# SchematicPULPiniMCU.net
KiCad netlist of a schematic drawn in Altium Designer
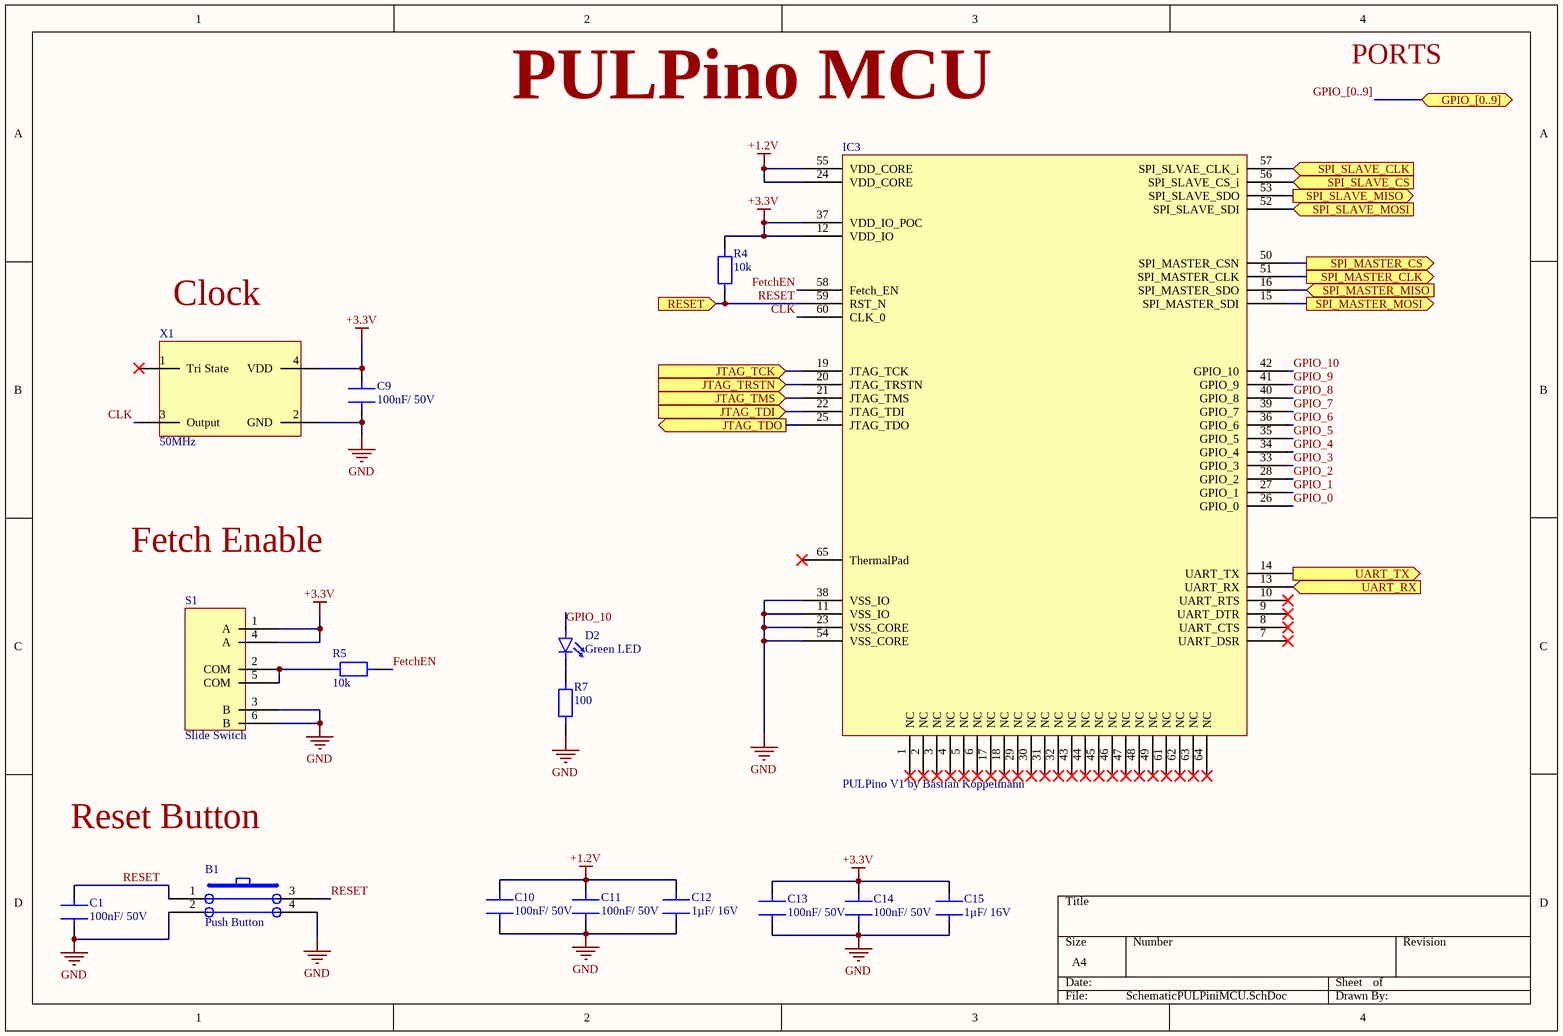
[diagram p0: SchematicPULPiniMCU.SchDoc]

(export (version "E")
  (design (tool "Eeschema 10.0.6"))
  (components
    (comp (ref "B1")
      (value "Push Button")
      (footprint "PUSH Switch")
      (description "PTS647SM50SMTR2LFS")
      (libsource (lib "upbracing_library") (part "Push Button PTS647SM50SMTR2LFS"))
    )
    (comp (ref "C1")
      (value "100nF/ 50V")
      (footprint "C0603")
      (description "C0603/C0805")
      (libsource (lib "upbracing_library") (part "C 100nF/ 50V"))
    )
    (comp (ref "C9")
      (value "100nF/ 50V")
      (footprint "C0603")
      (description "C0603/C0805")
      (libsource (lib "upbracing_library") (part "C 100nF/ 50V"))
    )
    (comp (ref "C10")
      (value "100nF/ 50V")
      (footprint "C0603")
      (description "C0603/C0805")
      (libsource (lib "upbracing_library") (part "C 100nF/ 50V"))
    )
    (comp (ref "C11")
      (value "100nF/ 50V")
      (footprint "C0603")
      (description "C0603/C0805")
      (libsource (lib "upbracing_library") (part "C 100nF/ 50V"))
    )
    (comp (ref "C12")
      (value "1µF/ 16V")
      (footprint "C0603")
      (description "C0603/C0805")
      (libsource (lib "upbracing_library") (part "C 1µF/ 16V"))
    )
    (comp (ref "C13")
      (value "100nF/ 50V")
      (footprint "C0603")
      (description "C0603/C0805")
      (libsource (lib "upbracing_library") (part "C 100nF/ 50V"))
    )
    (comp (ref "C14")
      (value "100nF/ 50V")
      (footprint "C0603")
      (description "C0603/C0805")
      (libsource (lib "upbracing_library") (part "C 100nF/ 50V"))
    )
    (comp (ref "C15")
      (value "1µF/ 16V")
      (footprint "C0603")
      (description "C0603/C0805")
      (libsource (lib "upbracing_library") (part "C 1µF/ 16V"))
    )
    (comp (ref "D2")
      (value "Green LED")
      (footprint "LED_0805")
      (description "Status LED")
      (libsource (lib "upbracing_library") (part "LED 0805"))
    )
    (comp (ref "IC3")
      (value "PULPino V1 by Bastian Koppelmann")
      (footprint "MQFN 64-Lead 9mm P=0.5mm")
      (description "Version 1 PULPino by Bastian Koppelmann")
      (libsource (lib "upbracing_library") (part "MCU PULPino V1 QFN64"))
    )
    (comp (ref "R4")
      (value "10k")
      (footprint "R0603")
      (description "0805")
      (libsource (lib "upbracing_library") (part "RES_10k"))
    )
    (comp (ref "R5")
      (value "10k")
      (footprint "R0603")
      (description "0805")
      (libsource (lib "upbracing_library") (part "RES_10k"))
    )
    (comp (ref "R7")
      (value "100")
      (footprint "R0603")
      (description "0603/0805")
      (libsource (lib "upbracing_library") (part "RES_100"))
    )
    (comp (ref "S1")
      (value "Slide Switch")
      (footprint "Slide Switch WE 452403012014")
      (description "Slide Switch, WE 452403012014")
      (libsource (lib "upbracing_library") (part "Slide Switch WE 452403012014"))
    )
    (comp (ref "X1")
      (value "50MHz")
      (footprint "QFN 2520 SiT1602 Oscillators 2.5x2.0mm")
      (description "Oscillator 50MHz. Pin 1 NC")
      (libsource (lib "upbracing_library") (part "SiT1602BC-11-33N-50.000000"))
    )
  )
  (nets
    (net (code "1") (name "+1.2V") (class "Default")
      (node (ref "C10") (pin "2") (pinfunction "2_2") (pintype "passive"))
      (node (ref "C11") (pin "2") (pinfunction "2_2") (pintype "passive"))
      (node (ref "C12") (pin "2") (pinfunction "2_2") (pintype "passive"))
      (node (ref "IC3") (pin "24") (pinfunction "VDD_CORE_24") (pintype "passive"))
      (node (ref "IC3") (pin "55") (pinfunction "VDD_CORE_55") (pintype "passive"))
    )
    (net (code "2") (name "+3.3V") (class "Default")
      (node (ref "C13") (pin "2") (pinfunction "2_2") (pintype "passive"))
      (node (ref "C14") (pin "2") (pinfunction "2_2") (pintype "passive"))
      (node (ref "C15") (pin "2") (pinfunction "2_2") (pintype "passive"))
      (node (ref "C9") (pin "1") (pinfunction "1_1") (pintype "passive"))
      (node (ref "IC3") (pin "12") (pinfunction "VDD_IO_12") (pintype "passive"))
      (node (ref "IC3") (pin "37") (pinfunction "VDD_IO_POC_37") (pintype "passive"))
      (node (ref "R4") (pin "2") (pinfunction "2_2") (pintype "passive"))
      (node (ref "S1") (pin "1") (pinfunction "A_1") (pintype "passive"))
      (node (ref "S1") (pin "4") (pinfunction "A_4") (pintype "passive"))
      (node (ref "X1") (pin "4") (pinfunction "VDD_4") (pintype "passive"))
    )
    (net (code "3") (name "/CLK") (class "Default")
      (node (ref "IC3") (pin "60") (pinfunction "CLK_0_60") (pintype "passive"))
      (node (ref "X1") (pin "3") (pinfunction "Output_3") (pintype "passive"))
    )
    (net (code "4") (name "/FetchEN") (class "Default")
      (node (ref "IC3") (pin "58") (pinfunction "Fetch_EN_58") (pintype "passive"))
      (node (ref "R5") (pin "2") (pinfunction "2_2") (pintype "passive"))
    )
    (net (code "5") (name "/GPIO_0") (class "Default")
      (node (ref "IC3") (pin "26") (pinfunction "GPIO_0_26") (pintype "passive"))
    )
    (net (code "6") (name "/GPIO_1") (class "Default")
      (node (ref "IC3") (pin "27") (pinfunction "GPIO_1_27") (pintype "passive"))
    )
    (net (code "7") (name "/GPIO_2") (class "Default")
      (node (ref "IC3") (pin "28") (pinfunction "GPIO_2_28") (pintype "passive"))
    )
    (net (code "8") (name "/GPIO_3") (class "Default")
      (node (ref "IC3") (pin "33") (pinfunction "GPIO_3_33") (pintype "passive"))
    )
    (net (code "9") (name "/GPIO_4") (class "Default")
      (node (ref "IC3") (pin "34") (pinfunction "GPIO_4_34") (pintype "passive"))
    )
    (net (code "10") (name "/GPIO_5") (class "Default")
      (node (ref "IC3") (pin "35") (pinfunction "GPIO_5_35") (pintype "passive"))
    )
    (net (code "11") (name "/GPIO_6") (class "Default")
      (node (ref "IC3") (pin "36") (pinfunction "GPIO_6_36") (pintype "passive"))
    )
    (net (code "12") (name "/GPIO_7") (class "Default")
      (node (ref "IC3") (pin "39") (pinfunction "GPIO_7_39") (pintype "passive"))
    )
    (net (code "13") (name "/GPIO_8") (class "Default")
      (node (ref "IC3") (pin "40") (pinfunction "GPIO_8_40") (pintype "passive"))
    )
    (net (code "14") (name "/GPIO_9") (class "Default")
      (node (ref "IC3") (pin "41") (pinfunction "GPIO_9_41") (pintype "passive"))
    )
    (net (code "15") (name "/GPIO_10") (class "Default")
      (node (ref "D2") (pin "1") (pinfunction "1_1") (pintype "passive"))
      (node (ref "IC3") (pin "42") (pinfunction "GPIO_10_42") (pintype "passive"))
    )
    (net (code "17") (name "/JTAG_TCK") (class "Default")
      (node (ref "IC3") (pin "19") (pinfunction "JTAG_TCK_19") (pintype "passive"))
    )
    (net (code "18") (name "/JTAG_TDI") (class "Default")
      (node (ref "IC3") (pin "22") (pinfunction "JTAG_TDI_22") (pintype "passive"))
    )
    (net (code "19") (name "/JTAG_TDO") (class "Default")
      (node (ref "IC3") (pin "25") (pinfunction "JTAG_TDO_25") (pintype "passive"))
    )
    (net (code "20") (name "/JTAG_TMS") (class "Default")
      (node (ref "IC3") (pin "21") (pinfunction "JTAG_TMS_21") (pintype "passive"))
    )
    (net (code "21") (name "/JTAG_TRSTN") (class "Default")
      (node (ref "IC3") (pin "20") (pinfunction "JTAG_TRSTN_20") (pintype "passive"))
    )
    (net (code "22") (name "/RESET") (class "Default")
      (node (ref "B1") (pin "1") (pinfunction "1_1") (pintype "passive"))
      (node (ref "B1") (pin "3") (pinfunction "1_3") (pintype "passive"))
      (node (ref "C1") (pin "1") (pinfunction "1_1") (pintype "passive"))
      (node (ref "IC3") (pin "59") (pinfunction "RST_N_59") (pintype "passive"))
      (node (ref "R4") (pin "1") (pinfunction "1_1") (pintype "passive"))
    )
    (net (code "23") (name "/SPI_MASTER_CLK") (class "Default")
      (node (ref "IC3") (pin "51") (pinfunction "SPI_MASTER_CLK_51") (pintype "passive"))
    )
    (net (code "24") (name "/SPI_MASTER_CS") (class "Default")
      (node (ref "IC3") (pin "50") (pinfunction "SPI_MASTER_CSN_50") (pintype "passive"))
    )
    (net (code "25") (name "/SPI_MASTER_MISO") (class "Default")
      (node (ref "IC3") (pin "16") (pinfunction "SPI_MASTER_SDO_16") (pintype "passive"))
    )
    (net (code "26") (name "/SPI_MASTER_MOSI") (class "Default")
      (node (ref "IC3") (pin "15") (pinfunction "SPI_MASTER_SDI_15") (pintype "passive"))
    )
    (net (code "27") (name "/SPI_SLAVE_CLK") (class "Default")
      (node (ref "IC3") (pin "57") (pinfunction "SPI_SLVAE_CLK_i_57") (pintype "passive"))
    )
    (net (code "28") (name "/SPI_SLAVE_CS") (class "Default")
      (node (ref "IC3") (pin "56") (pinfunction "SPI_SLAVE_CS_i_56") (pintype "passive"))
    )
    (net (code "29") (name "/SPI_SLAVE_MISO") (class "Default")
      (node (ref "IC3") (pin "53") (pinfunction "SPI_SLAVE_SDO_53") (pintype "passive"))
    )
    (net (code "30") (name "/SPI_SLAVE_MOSI") (class "Default")
      (node (ref "IC3") (pin "52") (pinfunction "SPI_SLAVE_SDI_52") (pintype "passive"))
    )
    (net (code "31") (name "/UART_RX") (class "Default")
      (node (ref "IC3") (pin "13") (pinfunction "UART_RX_13") (pintype "passive"))
    )
    (net (code "32") (name "/UART_TX") (class "Default")
      (node (ref "IC3") (pin "14") (pinfunction "UART_TX_14") (pintype "passive"))
    )
    (net (code "33") (name "GND") (class "Default")
      (node (ref "B1") (pin "2") (pinfunction "2_2") (pintype "passive"))
      (node (ref "B1") (pin "4") (pinfunction "2_4") (pintype "passive"))
      (node (ref "C1") (pin "2") (pinfunction "2_2") (pintype "passive"))
      (node (ref "C10") (pin "1") (pinfunction "1_1") (pintype "passive"))
      (node (ref "C11") (pin "1") (pinfunction "1_1") (pintype "passive"))
      (node (ref "C12") (pin "1") (pinfunction "1_1") (pintype "passive"))
      (node (ref "C13") (pin "1") (pinfunction "1_1") (pintype "passive"))
      (node (ref "C14") (pin "1") (pinfunction "1_1") (pintype "passive"))
      (node (ref "C15") (pin "1") (pinfunction "1_1") (pintype "passive"))
      (node (ref "C9") (pin "2") (pinfunction "2_2") (pintype "passive"))
      (node (ref "IC3") (pin "11") (pinfunction "VSS_IO_11") (pintype "passive"))
      (node (ref "IC3") (pin "23") (pinfunction "VSS_CORE_23") (pintype "passive"))
      (node (ref "IC3") (pin "38") (pinfunction "VSS_IO_38") (pintype "passive"))
      (node (ref "IC3") (pin "54") (pinfunction "VSS_CORE_54") (pintype "passive"))
      (node (ref "R7") (pin "1") (pinfunction "1_1") (pintype "passive"))
      (node (ref "S1") (pin "3") (pinfunction "B_3") (pintype "passive"))
      (node (ref "S1") (pin "6") (pinfunction "B_6") (pintype "passive"))
      (node (ref "X1") (pin "2") (pinfunction "GND_2") (pintype "passive"))
    )
    (net (code "34") (name "Net-(D2-Pad2)") (class "Default")
      (node (ref "D2") (pin "2") (pinfunction "2_2") (pintype "passive"))
      (node (ref "R7") (pin "2") (pinfunction "2_2") (pintype "passive"))
    )
    (net (code "35") (name "Net-(R5-Pad1)") (class "Default")
      (node (ref "R5") (pin "1") (pinfunction "1_1") (pintype "passive"))
      (node (ref "S1") (pin "2") (pinfunction "COM_2") (pintype "passive"))
      (node (ref "S1") (pin "5") (pinfunction "COM_5") (pintype "passive"))
    )
    (net (code "36") (name "unconnected-(IC3-NC-Pad1)") (class "Default")
      (node (ref "IC3") (pin "1") (pinfunction "NC_1") (pintype "passive+no_connect"))
    )
    (net (code "37") (name "unconnected-(IC3-NC-Pad2)") (class "Default")
      (node (ref "IC3") (pin "2") (pinfunction "NC_2") (pintype "passive+no_connect"))
    )
    (net (code "38") (name "unconnected-(IC3-NC-Pad3)") (class "Default")
      (node (ref "IC3") (pin "3") (pinfunction "NC_3") (pintype "passive+no_connect"))
    )
    (net (code "39") (name "unconnected-(IC3-NC-Pad4)") (class "Default")
      (node (ref "IC3") (pin "4") (pinfunction "NC_4") (pintype "passive+no_connect"))
    )
    (net (code "40") (name "unconnected-(IC3-NC-Pad5)") (class "Default")
      (node (ref "IC3") (pin "5") (pinfunction "NC_5") (pintype "passive+no_connect"))
    )
    (net (code "41") (name "unconnected-(IC3-NC-Pad6)") (class "Default")
      (node (ref "IC3") (pin "6") (pinfunction "NC_6") (pintype "passive+no_connect"))
    )
    (net (code "42") (name "unconnected-(IC3-NC-Pad17)") (class "Default")
      (node (ref "IC3") (pin "17") (pinfunction "NC_17") (pintype "passive+no_connect"))
    )
    (net (code "43") (name "unconnected-(IC3-NC-Pad18)") (class "Default")
      (node (ref "IC3") (pin "18") (pinfunction "NC_18") (pintype "passive+no_connect"))
    )
    (net (code "44") (name "unconnected-(IC3-NC-Pad29)") (class "Default")
      (node (ref "IC3") (pin "29") (pinfunction "NC_29") (pintype "passive+no_connect"))
    )
    (net (code "45") (name "unconnected-(IC3-NC-Pad30)") (class "Default")
      (node (ref "IC3") (pin "30") (pinfunction "NC_30") (pintype "passive+no_connect"))
    )
    (net (code "46") (name "unconnected-(IC3-NC-Pad31)") (class "Default")
      (node (ref "IC3") (pin "31") (pinfunction "NC_31") (pintype "passive+no_connect"))
    )
    (net (code "47") (name "unconnected-(IC3-NC-Pad32)") (class "Default")
      (node (ref "IC3") (pin "32") (pinfunction "NC_32") (pintype "passive+no_connect"))
    )
    (net (code "48") (name "unconnected-(IC3-NC-Pad43)") (class "Default")
      (node (ref "IC3") (pin "43") (pinfunction "NC_43") (pintype "passive+no_connect"))
    )
    (net (code "49") (name "unconnected-(IC3-NC-Pad44)") (class "Default")
      (node (ref "IC3") (pin "44") (pinfunction "NC_44") (pintype "passive+no_connect"))
    )
    (net (code "50") (name "unconnected-(IC3-NC-Pad45)") (class "Default")
      (node (ref "IC3") (pin "45") (pinfunction "NC_45") (pintype "passive+no_connect"))
    )
    (net (code "51") (name "unconnected-(IC3-NC-Pad46)") (class "Default")
      (node (ref "IC3") (pin "46") (pinfunction "NC_46") (pintype "passive+no_connect"))
    )
    (net (code "52") (name "unconnected-(IC3-NC-Pad47)") (class "Default")
      (node (ref "IC3") (pin "47") (pinfunction "NC_47") (pintype "passive+no_connect"))
    )
    (net (code "53") (name "unconnected-(IC3-NC-Pad48)") (class "Default")
      (node (ref "IC3") (pin "48") (pinfunction "NC_48") (pintype "passive+no_connect"))
    )
    (net (code "54") (name "unconnected-(IC3-NC-Pad49)") (class "Default")
      (node (ref "IC3") (pin "49") (pinfunction "NC_49") (pintype "passive+no_connect"))
    )
    (net (code "55") (name "unconnected-(IC3-NC-Pad61)") (class "Default")
      (node (ref "IC3") (pin "61") (pinfunction "NC_61") (pintype "passive+no_connect"))
    )
    (net (code "56") (name "unconnected-(IC3-NC-Pad62)") (class "Default")
      (node (ref "IC3") (pin "62") (pinfunction "NC_62") (pintype "passive+no_connect"))
    )
    (net (code "57") (name "unconnected-(IC3-NC-Pad63)") (class "Default")
      (node (ref "IC3") (pin "63") (pinfunction "NC_63") (pintype "passive+no_connect"))
    )
    (net (code "58") (name "unconnected-(IC3-NC-Pad64)") (class "Default")
      (node (ref "IC3") (pin "64") (pinfunction "NC_64") (pintype "passive+no_connect"))
    )
    (net (code "59") (name "unconnected-(IC3-ThermalPad-Pad65)") (class "Default")
      (node (ref "IC3") (pin "65") (pinfunction "ThermalPad_65") (pintype "passive+no_connect"))
    )
    (net (code "60") (name "unconnected-(IC3-UART_CTS-Pad8)") (class "Default")
      (node (ref "IC3") (pin "8") (pinfunction "UART_CTS_8") (pintype "passive+no_connect"))
    )
    (net (code "61") (name "unconnected-(IC3-UART_DSR-Pad7)") (class "Default")
      (node (ref "IC3") (pin "7") (pinfunction "UART_DSR_7") (pintype "passive+no_connect"))
    )
    (net (code "62") (name "unconnected-(IC3-UART_DTR-Pad9)") (class "Default")
      (node (ref "IC3") (pin "9") (pinfunction "UART_DTR_9") (pintype "passive+no_connect"))
    )
    (net (code "63") (name "unconnected-(IC3-UART_RTS-Pad10)") (class "Default")
      (node (ref "IC3") (pin "10") (pinfunction "UART_RTS_10") (pintype "passive+no_connect"))
    )
    (net (code "64") (name "unconnected-(X1-Tri_State-Pad1)") (class "Default")
      (node (ref "X1") (pin "1") (pinfunction "Tri_State_1") (pintype "passive+no_connect"))
    )
  )
)
